# armstrap_eagle-tester_1_0_0.net
KiCad netlist of a schematic drawn in EAGLE
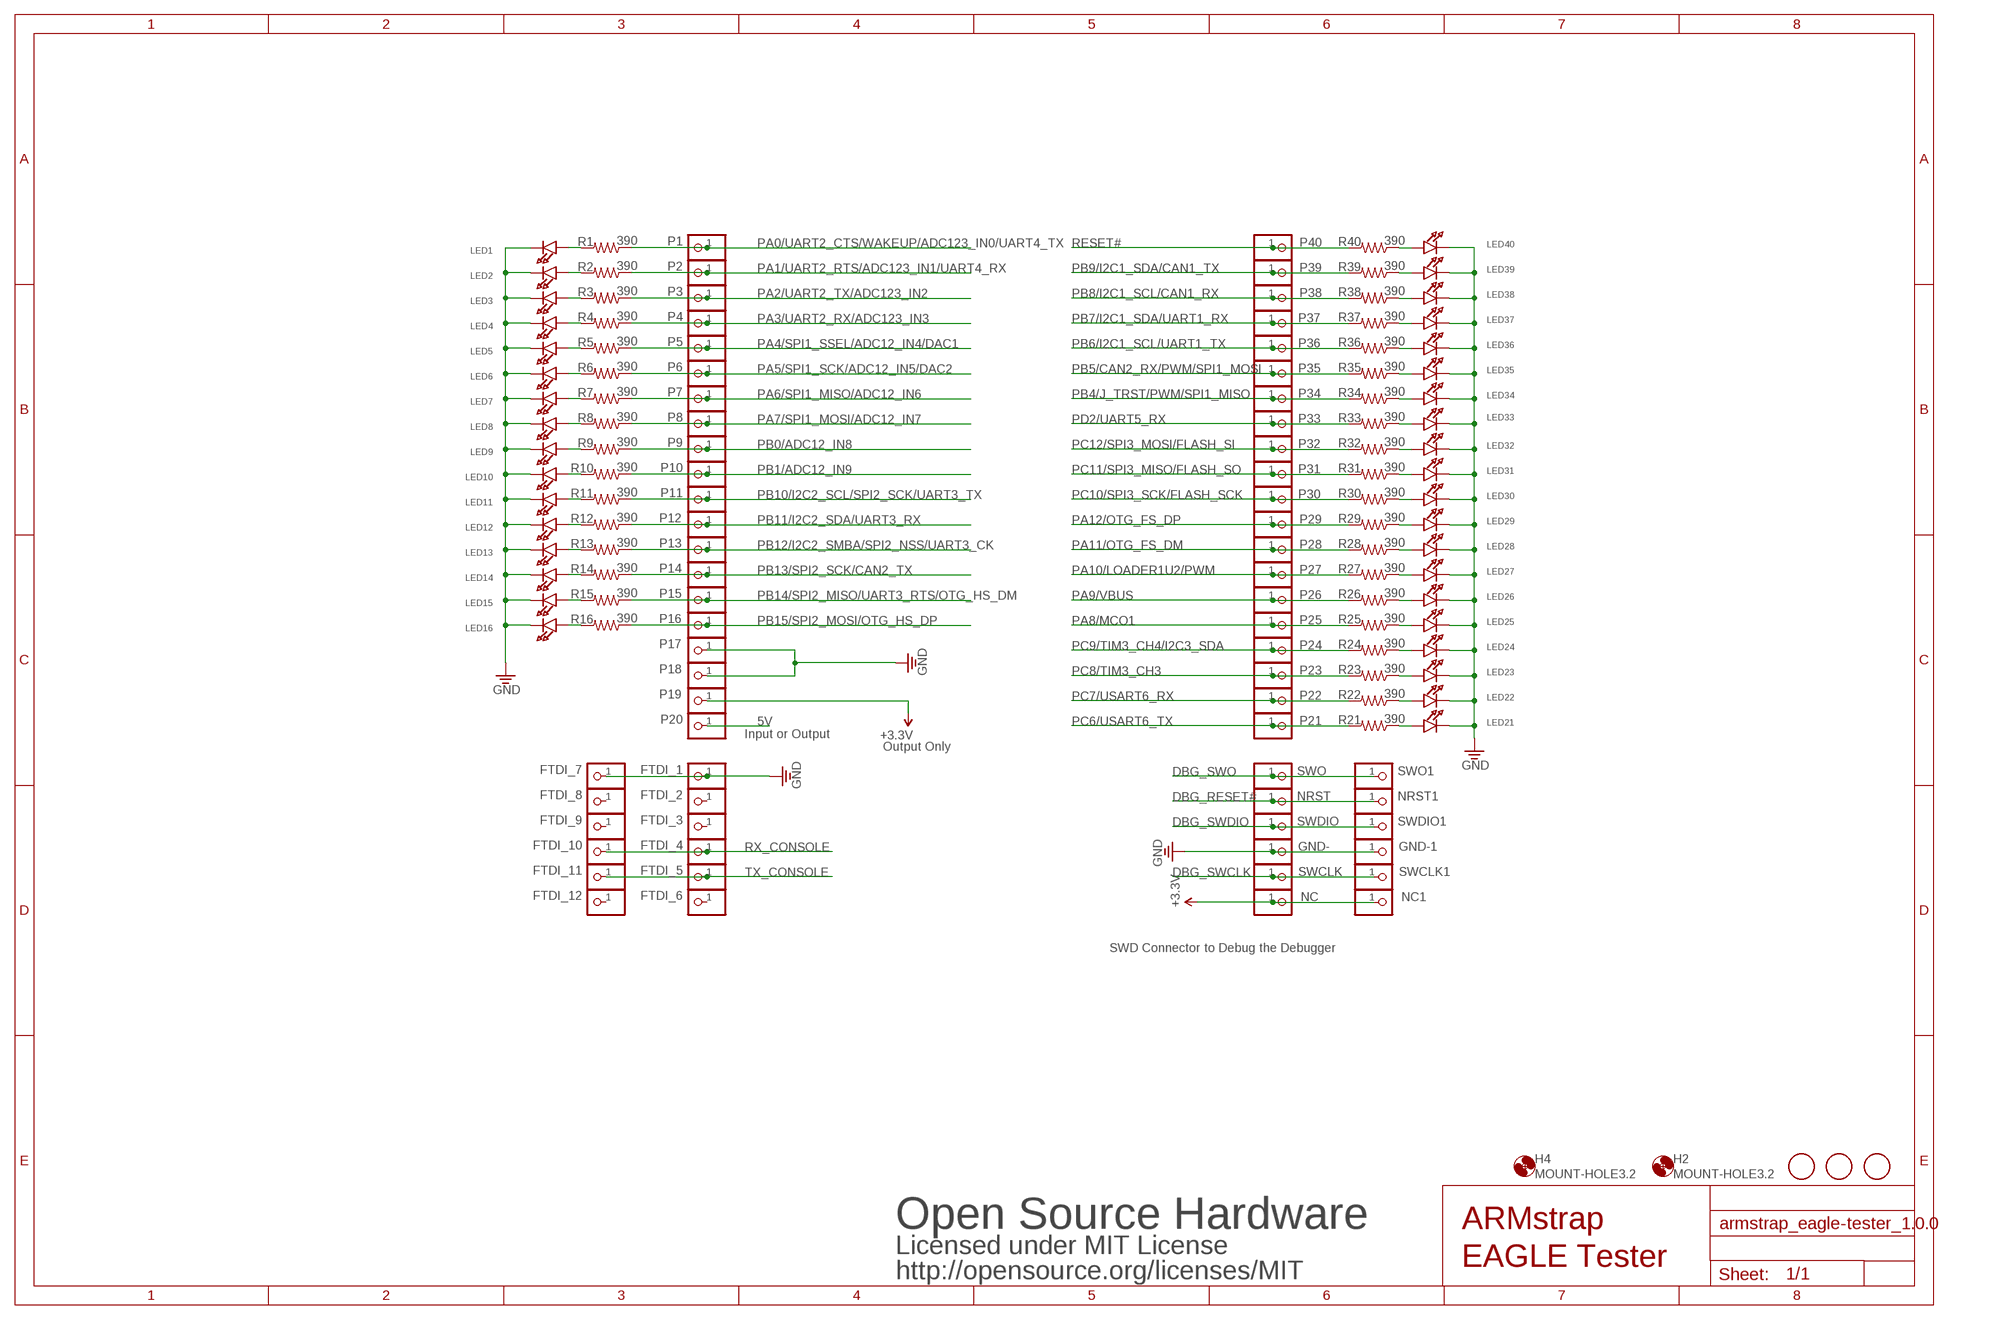
[diagram p0: schematic, sheet 1]

(export (version "E")
  (design (tool "Eeschema 10.0.6"))
  (components
    (comp (ref "FID2")
      (value "FIDUCIAL")
      (footprint "eagle-import:FIDUCIAL_1MM")
      (libsource (lib "eagle-import") (part "FIDUCIAL"))
    )
    (comp (ref "FID3")
      (value "FIDUCIAL")
      (footprint "eagle-import:FIDUCIAL_1MM")
      (libsource (lib "eagle-import") (part "FIDUCIAL"))
    )
    (comp (ref "FID4")
      (value "FIDUCIAL")
      (footprint "eagle-import:FIDUCIAL_1MM")
      (libsource (lib "eagle-import") (part "FIDUCIAL"))
    )
    (comp (ref "FTDI_1")
      (value "PINHD-1X1")
      (footprint "eagle-import:1X01")
      (libsource (lib "eagle-import") (part "PINHD-1X1"))
    )
    (comp (ref "FTDI_2")
      (value "PINHD-1X1")
      (footprint "eagle-import:1X01")
      (libsource (lib "eagle-import") (part "PINHD-1X1"))
    )
    (comp (ref "FTDI_3")
      (value "PINHD-1X1")
      (footprint "eagle-import:1X01")
      (libsource (lib "eagle-import") (part "PINHD-1X1"))
    )
    (comp (ref "FTDI_4")
      (value "PINHD-1X1")
      (footprint "eagle-import:1X01")
      (libsource (lib "eagle-import") (part "PINHD-1X1"))
    )
    (comp (ref "FTDI_5")
      (value "PINHD-1X1")
      (footprint "eagle-import:1X01")
      (libsource (lib "eagle-import") (part "PINHD-1X1"))
    )
    (comp (ref "FTDI_6")
      (value "PINHD-1X1")
      (footprint "eagle-import:1X01")
      (libsource (lib "eagle-import") (part "PINHD-1X1"))
    )
    (comp (ref "FTDI_7")
      (value "PINHD-1X1")
      (footprint "eagle-import:1X01")
      (libsource (lib "eagle-import") (part "PINHD-1X1"))
    )
    (comp (ref "FTDI_8")
      (value "PINHD-1X1")
      (footprint "eagle-import:1X01")
      (libsource (lib "eagle-import") (part "PINHD-1X1"))
    )
    (comp (ref "FTDI_9")
      (value "PINHD-1X1")
      (footprint "eagle-import:1X01")
      (libsource (lib "eagle-import") (part "PINHD-1X1"))
    )
    (comp (ref "FTDI_10")
      (value "PINHD-1X1")
      (footprint "eagle-import:1X01")
      (libsource (lib "eagle-import") (part "PINHD-1X1"))
    )
    (comp (ref "FTDI_11")
      (value "PINHD-1X1")
      (footprint "eagle-import:1X01")
      (libsource (lib "eagle-import") (part "PINHD-1X1"))
    )
    (comp (ref "FTDI_12")
      (value "PINHD-1X1")
      (footprint "eagle-import:1X01")
      (libsource (lib "eagle-import") (part "PINHD-1X1"))
    )
    (comp (ref "GND-")
      (value "PINHD-1X1")
      (footprint "eagle-import:1X01")
      (libsource (lib "eagle-import") (part "PINHD-1X1"))
    )
    (comp (ref "GND-1")
      (value "PINHD-1X1")
      (footprint "eagle-import:1X01")
      (libsource (lib "eagle-import") (part "PINHD-1X1"))
    )
    (comp (ref "H2")
      (value "MOUNT-HOLE3.2")
      (footprint "eagle-import:3,2")
      (libsource (lib "eagle-import") (part "MOUNT-HOLE3.2"))
    )
    (comp (ref "H4")
      (value "MOUNT-HOLE3.2")
      (footprint "eagle-import:3,2")
      (libsource (lib "eagle-import") (part "MOUNT-HOLE3.2"))
    )
    (comp (ref "LED1")
      (value "APT3216QBC/D")
      (footprint "eagle-import:CHIPLED_1206")
      (libsource (lib "eagle-import") (part "LED1206"))
    )
    (comp (ref "LED2")
      (value "APT3216QBC/D")
      (footprint "eagle-import:CHIPLED_1206")
      (libsource (lib "eagle-import") (part "LED1206"))
    )
    (comp (ref "LED3")
      (value "APT3216QBC/D")
      (footprint "eagle-import:CHIPLED_1206")
      (libsource (lib "eagle-import") (part "LED1206"))
    )
    (comp (ref "LED4")
      (value "APT3216QBC/D")
      (footprint "eagle-import:CHIPLED_1206")
      (libsource (lib "eagle-import") (part "LED1206"))
    )
    (comp (ref "LED5")
      (value "APT3216QBC/D")
      (footprint "eagle-import:CHIPLED_1206")
      (libsource (lib "eagle-import") (part "LED1206"))
    )
    (comp (ref "LED6")
      (value "APT3216QBC/D")
      (footprint "eagle-import:CHIPLED_1206")
      (libsource (lib "eagle-import") (part "LED1206"))
    )
    (comp (ref "LED7")
      (value "APT3216QBC/D")
      (footprint "eagle-import:CHIPLED_1206")
      (libsource (lib "eagle-import") (part "LED1206"))
    )
    (comp (ref "LED8")
      (value "APT3216QBC/D")
      (footprint "eagle-import:CHIPLED_1206")
      (libsource (lib "eagle-import") (part "LED1206"))
    )
    (comp (ref "LED9")
      (value "APT3216QBC/D")
      (footprint "eagle-import:CHIPLED_1206")
      (libsource (lib "eagle-import") (part "LED1206"))
    )
    (comp (ref "LED10")
      (value "APT3216QBC/D")
      (footprint "eagle-import:CHIPLED_1206")
      (libsource (lib "eagle-import") (part "LED1206"))
    )
    (comp (ref "LED11")
      (value "APT3216QBC/D")
      (footprint "eagle-import:CHIPLED_1206")
      (libsource (lib "eagle-import") (part "LED1206"))
    )
    (comp (ref "LED12")
      (value "APT3216QBC/D")
      (footprint "eagle-import:CHIPLED_1206")
      (libsource (lib "eagle-import") (part "LED1206"))
    )
    (comp (ref "LED13")
      (value "APT3216QBC/D")
      (footprint "eagle-import:CHIPLED_1206")
      (libsource (lib "eagle-import") (part "LED1206"))
    )
    (comp (ref "LED14")
      (value "APT3216QBC/D")
      (footprint "eagle-import:CHIPLED_1206")
      (libsource (lib "eagle-import") (part "LED1206"))
    )
    (comp (ref "LED15")
      (value "APT3216QBC/D")
      (footprint "eagle-import:CHIPLED_1206")
      (libsource (lib "eagle-import") (part "LED1206"))
    )
    (comp (ref "LED16")
      (value "APT3216QBC/D")
      (footprint "eagle-import:CHIPLED_1206")
      (libsource (lib "eagle-import") (part "LED1206"))
    )
    (comp (ref "LED21")
      (value "APT3216QBC/D")
      (footprint "eagle-import:CHIPLED_1206")
      (libsource (lib "eagle-import") (part "LED1206"))
    )
    (comp (ref "LED22")
      (value "APT3216QBC/D")
      (footprint "eagle-import:CHIPLED_1206")
      (libsource (lib "eagle-import") (part "LED1206"))
    )
    (comp (ref "LED23")
      (value "APT3216QBC/D")
      (footprint "eagle-import:CHIPLED_1206")
      (libsource (lib "eagle-import") (part "LED1206"))
    )
    (comp (ref "LED24")
      (value "APT3216QBC/D")
      (footprint "eagle-import:CHIPLED_1206")
      (libsource (lib "eagle-import") (part "LED1206"))
    )
    (comp (ref "LED25")
      (value "APT3216QBC/D")
      (footprint "eagle-import:CHIPLED_1206")
      (libsource (lib "eagle-import") (part "LED1206"))
    )
    (comp (ref "LED26")
      (value "APT3216QBC/D")
      (footprint "eagle-import:CHIPLED_1206")
      (libsource (lib "eagle-import") (part "LED1206"))
    )
    (comp (ref "LED27")
      (value "APT3216QBC/D")
      (footprint "eagle-import:CHIPLED_1206")
      (libsource (lib "eagle-import") (part "LED1206"))
    )
    (comp (ref "LED28")
      (value "APT3216QBC/D")
      (footprint "eagle-import:CHIPLED_1206")
      (libsource (lib "eagle-import") (part "LED1206"))
    )
    (comp (ref "LED29")
      (value "APT3216QBC/D")
      (footprint "eagle-import:CHIPLED_1206")
      (libsource (lib "eagle-import") (part "LED1206"))
    )
    (comp (ref "LED30")
      (value "APT3216QBC/D")
      (footprint "eagle-import:CHIPLED_1206")
      (libsource (lib "eagle-import") (part "LED1206"))
    )
    (comp (ref "LED31")
      (value "APT3216QBC/D")
      (footprint "eagle-import:CHIPLED_1206")
      (libsource (lib "eagle-import") (part "LED1206"))
    )
    (comp (ref "LED32")
      (value "APT3216QBC/D")
      (footprint "eagle-import:CHIPLED_1206")
      (libsource (lib "eagle-import") (part "LED1206"))
    )
    (comp (ref "LED33")
      (value "APT3216QBC/D")
      (footprint "eagle-import:CHIPLED_1206")
      (libsource (lib "eagle-import") (part "LED1206"))
    )
    (comp (ref "LED34")
      (value "APT3216QBC/D")
      (footprint "eagle-import:CHIPLED_1206")
      (libsource (lib "eagle-import") (part "LED1206"))
    )
    (comp (ref "LED35")
      (value "APT3216QBC/D")
      (footprint "eagle-import:CHIPLED_1206")
      (libsource (lib "eagle-import") (part "LED1206"))
    )
    (comp (ref "LED36")
      (value "APT3216QBC/D")
      (footprint "eagle-import:CHIPLED_1206")
      (libsource (lib "eagle-import") (part "LED1206"))
    )
    (comp (ref "LED37")
      (value "APT3216QBC/D")
      (footprint "eagle-import:CHIPLED_1206")
      (libsource (lib "eagle-import") (part "LED1206"))
    )
    (comp (ref "LED38")
      (value "APT3216QBC/D")
      (footprint "eagle-import:CHIPLED_1206")
      (libsource (lib "eagle-import") (part "LED1206"))
    )
    (comp (ref "LED39")
      (value "APT3216QBC/D")
      (footprint "eagle-import:CHIPLED_1206")
      (libsource (lib "eagle-import") (part "LED1206"))
    )
    (comp (ref "LED40")
      (value "APT3216QBC/D")
      (footprint "eagle-import:CHIPLED_1206")
      (libsource (lib "eagle-import") (part "LED1206"))
    )
    (comp (ref "NC")
      (value "PINHD-1X1")
      (footprint "eagle-import:1X01")
      (libsource (lib "eagle-import") (part "PINHD-1X1"))
    )
    (comp (ref "NC1")
      (value "PINHD-1X1")
      (footprint "eagle-import:1X01")
      (libsource (lib "eagle-import") (part "PINHD-1X1"))
    )
    (comp (ref "NRST")
      (value "PINHD-1X1")
      (footprint "eagle-import:1X01")
      (libsource (lib "eagle-import") (part "PINHD-1X1"))
    )
    (comp (ref "NRST1")
      (value "PINHD-1X1")
      (footprint "eagle-import:1X01")
      (libsource (lib "eagle-import") (part "PINHD-1X1"))
    )
    (comp (ref "P1")
      (value "PINHD-1X1")
      (footprint "eagle-import:1X01")
      (libsource (lib "eagle-import") (part "PINHD-1X1"))
    )
    (comp (ref "P2")
      (value "PINHD-1X1")
      (footprint "eagle-import:1X01")
      (libsource (lib "eagle-import") (part "PINHD-1X1"))
    )
    (comp (ref "P3")
      (value "PINHD-1X1")
      (footprint "eagle-import:1X01")
      (libsource (lib "eagle-import") (part "PINHD-1X1"))
    )
    (comp (ref "P4")
      (value "PINHD-1X1")
      (footprint "eagle-import:1X01")
      (libsource (lib "eagle-import") (part "PINHD-1X1"))
    )
    (comp (ref "P5")
      (value "PINHD-1X1")
      (footprint "eagle-import:1X01")
      (libsource (lib "eagle-import") (part "PINHD-1X1"))
    )
    (comp (ref "P6")
      (value "PINHD-1X1")
      (footprint "eagle-import:1X01")
      (libsource (lib "eagle-import") (part "PINHD-1X1"))
    )
    (comp (ref "P7")
      (value "PINHD-1X1")
      (footprint "eagle-import:1X01")
      (libsource (lib "eagle-import") (part "PINHD-1X1"))
    )
    (comp (ref "P8")
      (value "PINHD-1X1")
      (footprint "eagle-import:1X01")
      (libsource (lib "eagle-import") (part "PINHD-1X1"))
    )
    (comp (ref "P9")
      (value "PINHD-1X1")
      (footprint "eagle-import:1X01")
      (libsource (lib "eagle-import") (part "PINHD-1X1"))
    )
    (comp (ref "P10")
      (value "PINHD-1X1")
      (footprint "eagle-import:1X01")
      (libsource (lib "eagle-import") (part "PINHD-1X1"))
    )
    (comp (ref "P11")
      (value "PINHD-1X1")
      (footprint "eagle-import:1X01")
      (libsource (lib "eagle-import") (part "PINHD-1X1"))
    )
    (comp (ref "P12")
      (value "PINHD-1X1")
      (footprint "eagle-import:1X01")
      (libsource (lib "eagle-import") (part "PINHD-1X1"))
    )
    (comp (ref "P13")
      (value "PINHD-1X1")
      (footprint "eagle-import:1X01")
      (libsource (lib "eagle-import") (part "PINHD-1X1"))
    )
    (comp (ref "P14")
      (value "PINHD-1X1")
      (footprint "eagle-import:1X01")
      (libsource (lib "eagle-import") (part "PINHD-1X1"))
    )
    (comp (ref "P15")
      (value "PINHD-1X1")
      (footprint "eagle-import:1X01")
      (libsource (lib "eagle-import") (part "PINHD-1X1"))
    )
    (comp (ref "P16")
      (value "PINHD-1X1")
      (footprint "eagle-import:1X01")
      (libsource (lib "eagle-import") (part "PINHD-1X1"))
    )
    (comp (ref "P17")
      (value "PINHD-1X1")
      (footprint "eagle-import:1X01")
      (libsource (lib "eagle-import") (part "PINHD-1X1"))
    )
    (comp (ref "P18")
      (value "PINHD-1X1")
      (footprint "eagle-import:1X01")
      (libsource (lib "eagle-import") (part "PINHD-1X1"))
    )
    (comp (ref "P19")
      (value "PINHD-1X1")
      (footprint "eagle-import:1X01")
      (libsource (lib "eagle-import") (part "PINHD-1X1"))
    )
    (comp (ref "P20")
      (value "PINHD-1X1")
      (footprint "eagle-import:1X01")
      (libsource (lib "eagle-import") (part "PINHD-1X1"))
    )
    (comp (ref "P21")
      (value "PINHD-1X1")
      (footprint "eagle-import:1X01")
      (libsource (lib "eagle-import") (part "PINHD-1X1"))
    )
    (comp (ref "P22")
      (value "PINHD-1X1")
      (footprint "eagle-import:1X01")
      (libsource (lib "eagle-import") (part "PINHD-1X1"))
    )
    (comp (ref "P23")
      (value "PINHD-1X1")
      (footprint "eagle-import:1X01")
      (libsource (lib "eagle-import") (part "PINHD-1X1"))
    )
    (comp (ref "P24")
      (value "PINHD-1X1")
      (footprint "eagle-import:1X01")
      (libsource (lib "eagle-import") (part "PINHD-1X1"))
    )
    (comp (ref "P25")
      (value "PINHD-1X1")
      (footprint "eagle-import:1X01")
      (libsource (lib "eagle-import") (part "PINHD-1X1"))
    )
    (comp (ref "P26")
      (value "PINHD-1X1")
      (footprint "eagle-import:1X01")
      (libsource (lib "eagle-import") (part "PINHD-1X1"))
    )
    (comp (ref "P27")
      (value "PINHD-1X1")
      (footprint "eagle-import:1X01")
      (libsource (lib "eagle-import") (part "PINHD-1X1"))
    )
    (comp (ref "P28")
      (value "PINHD-1X1")
      (footprint "eagle-import:1X01")
      (libsource (lib "eagle-import") (part "PINHD-1X1"))
    )
    (comp (ref "P29")
      (value "PINHD-1X1")
      (footprint "eagle-import:1X01")
      (libsource (lib "eagle-import") (part "PINHD-1X1"))
    )
    (comp (ref "P30")
      (value "PINHD-1X1")
      (footprint "eagle-import:1X01")
      (libsource (lib "eagle-import") (part "PINHD-1X1"))
    )
    (comp (ref "P31")
      (value "PINHD-1X1")
      (footprint "eagle-import:1X01")
      (libsource (lib "eagle-import") (part "PINHD-1X1"))
    )
    (comp (ref "P32")
      (value "PINHD-1X1")
      (footprint "eagle-import:1X01")
      (libsource (lib "eagle-import") (part "PINHD-1X1"))
    )
    (comp (ref "P33")
      (value "PINHD-1X1")
      (footprint "eagle-import:1X01")
      (libsource (lib "eagle-import") (part "PINHD-1X1"))
    )
    (comp (ref "P34")
      (value "PINHD-1X1")
      (footprint "eagle-import:1X01")
      (libsource (lib "eagle-import") (part "PINHD-1X1"))
    )
    (comp (ref "P35")
      (value "PINHD-1X1")
      (footprint "eagle-import:1X01")
      (libsource (lib "eagle-import") (part "PINHD-1X1"))
    )
    (comp (ref "P36")
      (value "PINHD-1X1")
      (footprint "eagle-import:1X01")
      (libsource (lib "eagle-import") (part "PINHD-1X1"))
    )
    (comp (ref "P37")
      (value "PINHD-1X1")
      (footprint "eagle-import:1X01")
      (libsource (lib "eagle-import") (part "PINHD-1X1"))
    )
    (comp (ref "P38")
      (value "PINHD-1X1")
      (footprint "eagle-import:1X01")
      (libsource (lib "eagle-import") (part "PINHD-1X1"))
    )
    (comp (ref "P39")
      (value "PINHD-1X1")
      (footprint "eagle-import:1X01")
      (libsource (lib "eagle-import") (part "PINHD-1X1"))
    )
    (comp (ref "P40")
      (value "PINHD-1X1")
      (footprint "eagle-import:1X01")
      (libsource (lib "eagle-import") (part "PINHD-1X1"))
    )
    (comp (ref "R1")
      (value "390")
      (footprint "eagle-import:0805")
      (libsource (lib "eagle-import") (part "RES0805"))
    )
    (comp (ref "R2")
      (value "390")
      (footprint "eagle-import:0805")
      (libsource (lib "eagle-import") (part "RES0805"))
    )
    (comp (ref "R3")
      (value "390")
      (footprint "eagle-import:0805")
      (libsource (lib "eagle-import") (part "RES0805"))
    )
    (comp (ref "R4")
      (value "390")
      (footprint "eagle-import:0805")
      (libsource (lib "eagle-import") (part "RES0805"))
    )
    (comp (ref "R5")
      (value "390")
      (footprint "eagle-import:0805")
      (libsource (lib "eagle-import") (part "RES0805"))
    )
    (comp (ref "R6")
      (value "390")
      (footprint "eagle-import:0805")
      (libsource (lib "eagle-import") (part "RES0805"))
    )
    (comp (ref "R7")
      (value "390")
      (footprint "eagle-import:0805")
      (libsource (lib "eagle-import") (part "RES0805"))
    )
    (comp (ref "R8")
      (value "390")
      (footprint "eagle-import:0805")
      (libsource (lib "eagle-import") (part "RES0805"))
    )
    (comp (ref "R9")
      (value "390")
      (footprint "eagle-import:0805")
      (libsource (lib "eagle-import") (part "RES0805"))
    )
    (comp (ref "R10")
      (value "390")
      (footprint "eagle-import:0805")
      (libsource (lib "eagle-import") (part "RES0805"))
    )
    (comp (ref "R11")
      (value "390")
      (footprint "eagle-import:0805")
      (libsource (lib "eagle-import") (part "RES0805"))
    )
    (comp (ref "R12")
      (value "390")
      (footprint "eagle-import:0805")
      (libsource (lib "eagle-import") (part "RES0805"))
    )
    (comp (ref "R13")
      (value "390")
      (footprint "eagle-import:0805")
      (libsource (lib "eagle-import") (part "RES0805"))
    )
    (comp (ref "R14")
      (value "390")
      (footprint "eagle-import:0805")
      (libsource (lib "eagle-import") (part "RES0805"))
    )
    (comp (ref "R15")
      (value "390")
      (footprint "eagle-import:0805")
      (libsource (lib "eagle-import") (part "RES0805"))
    )
    (comp (ref "R16")
      (value "390")
      (footprint "eagle-import:0805")
      (libsource (lib "eagle-import") (part "RES0805"))
    )
    (comp (ref "R21")
      (value "390")
      (footprint "eagle-import:0805")
      (libsource (lib "eagle-import") (part "RES0805"))
    )
    (comp (ref "R22")
      (value "390")
      (footprint "eagle-import:0805")
      (libsource (lib "eagle-import") (part "RES0805"))
    )
    (comp (ref "R23")
      (value "390")
      (footprint "eagle-import:0805")
      (libsource (lib "eagle-import") (part "RES0805"))
    )
    (comp (ref "R24")
      (value "390")
      (footprint "eagle-import:0805")
      (libsource (lib "eagle-import") (part "RES0805"))
    )
    (comp (ref "R25")
      (value "390")
      (footprint "eagle-import:0805")
      (libsource (lib "eagle-import") (part "RES0805"))
    )
    (comp (ref "R26")
      (value "390")
      (footprint "eagle-import:0805")
      (libsource (lib "eagle-import") (part "RES0805"))
    )
    (comp (ref "R27")
      (value "390")
      (footprint "eagle-import:0805")
      (libsource (lib "eagle-import") (part "RES0805"))
    )
    (comp (ref "R28")
      (value "390")
      (footprint "eagle-import:0805")
      (libsource (lib "eagle-import") (part "RES0805"))
    )
    (comp (ref "R29")
      (value "390")
      (footprint "eagle-import:0805")
      (libsource (lib "eagle-import") (part "RES0805"))
    )
    (comp (ref "R30")
      (value "390")
      (footprint "eagle-import:0805")
      (libsource (lib "eagle-import") (part "RES0805"))
    )
    (comp (ref "R31")
      (value "390")
      (footprint "eagle-import:0805")
      (libsource (lib "eagle-import") (part "RES0805"))
    )
    (comp (ref "R32")
      (value "390")
      (footprint "eagle-import:0805")
      (libsource (lib "eagle-import") (part "RES0805"))
    )
    (comp (ref "R33")
      (value "390")
      (footprint "eagle-import:0805")
      (libsource (lib "eagle-import") (part "RES0805"))
    )
    (comp (ref "R34")
      (value "390")
      (footprint "eagle-import:0805")
      (libsource (lib "eagle-import") (part "RES0805"))
    )
    (comp (ref "R35")
      (value "390")
      (footprint "eagle-import:0805")
      (libsource (lib "eagle-import") (part "RES0805"))
    )
    (comp (ref "R36")
      (value "390")
      (footprint "eagle-import:0805")
      (libsource (lib "eagle-import") (part "RES0805"))
    )
    (comp (ref "R37")
      (value "390")
      (footprint "eagle-import:0805")
      (libsource (lib "eagle-import") (part "RES0805"))
    )
    (comp (ref "R38")
      (value "390")
      (footprint "eagle-import:0805")
      (libsource (lib "eagle-import") (part "RES0805"))
    )
    (comp (ref "R39")
      (value "390")
      (footprint "eagle-import:0805")
      (libsource (lib "eagle-import") (part "RES0805"))
    )
    (comp (ref "R40")
      (value "390")
      (footprint "eagle-import:0805")
      (libsource (lib "eagle-import") (part "RES0805"))
    )
    (comp (ref "SWCLK")
      (value "PINHD-1X1")
      (footprint "eagle-import:1X01")
      (libsource (lib "eagle-import") (part "PINHD-1X1"))
    )
    (comp (ref "SWCLK1")
      (value "PINHD-1X1")
      (footprint "eagle-import:1X01")
      (libsource (lib "eagle-import") (part "PINHD-1X1"))
    )
    (comp (ref "SWDIO")
      (value "PINHD-1X1")
      (footprint "eagle-import:1X01")
      (libsource (lib "eagle-import") (part "PINHD-1X1"))
    )
    (comp (ref "SWDIO1")
      (value "PINHD-1X1")
      (footprint "eagle-import:1X01")
      (libsource (lib "eagle-import") (part "PINHD-1X1"))
    )
    (comp (ref "SWO")
      (value "PINHD-1X1")
      (footprint "eagle-import:1X01")
      (libsource (lib "eagle-import") (part "PINHD-1X1"))
    )
    (comp (ref "SWO1")
      (value "PINHD-1X1")
      (footprint "eagle-import:1X01")
      (libsource (lib "eagle-import") (part "PINHD-1X1"))
    )
  )
  (nets
    (net (code "1") (name "+3.3V") (class "Default")
      (node (ref "NC") (pin "1") (pinfunction "1_1") (pintype "passive"))
      (node (ref "NC1") (pin "1") (pinfunction "1_1") (pintype "passive"))
      (node (ref "P19") (pin "1") (pinfunction "1_1") (pintype "passive"))
    )
    (net (code "2") (name "/5V") (class "Default")
      (node (ref "P20") (pin "1") (pinfunction "1_1") (pintype "passive"))
    )
    (net (code "3") (name "/DBG_RESET#") (class "Default")
      (node (ref "NRST") (pin "1") (pinfunction "1_1") (pintype "passive"))
      (node (ref "NRST1") (pin "1") (pinfunction "1_1") (pintype "passive"))
    )
    (net (code "4") (name "/DBG_SWCLK") (class "Default")
      (node (ref "SWCLK") (pin "1") (pinfunction "1_1") (pintype "passive"))
      (node (ref "SWCLK1") (pin "1") (pinfunction "1_1") (pintype "passive"))
    )
    (net (code "5") (name "/DBG_SWDIO") (class "Default")
      (node (ref "SWDIO") (pin "1") (pinfunction "1_1") (pintype "passive"))
      (node (ref "SWDIO1") (pin "1") (pinfunction "1_1") (pintype "passive"))
    )
    (net (code "6") (name "/DBG_SWO") (class "Default")
      (node (ref "SWO") (pin "1") (pinfunction "1_1") (pintype "passive"))
      (node (ref "SWO1") (pin "1") (pinfunction "1_1") (pintype "passive"))
    )
    (net (code "7") (name "/PA0{slash}UART2_CTS{slash}WAKEUP{slash}ADC123_IN0{slash}UART4_TX") (class "Default")
      (node (ref "P1") (pin "1") (pinfunction "1_1") (pintype "passive"))
      (node (ref "R1") (pin "1") (pinfunction "1_1") (pintype "passive"))
    )
    (net (code "8") (name "/PA1{slash}UART2_RTS{slash}ADC123_IN1{slash}UART4_RX") (class "Default")
      (node (ref "P2") (pin "1") (pinfunction "1_1") (pintype "passive"))
      (node (ref "R2") (pin "1") (pinfunction "1_1") (pintype "passive"))
    )
    (net (code "9") (name "/PA2{slash}UART2_TX{slash}ADC123_IN2") (class "Default")
      (node (ref "P3") (pin "1") (pinfunction "1_1") (pintype "passive"))
      (node (ref "R3") (pin "1") (pinfunction "1_1") (pintype "passive"))
    )
    (net (code "10") (name "/PA3{slash}UART2_RX{slash}ADC123_IN3") (class "Default")
      (node (ref "P4") (pin "1") (pinfunction "1_1") (pintype "passive"))
      (node (ref "R4") (pin "1") (pinfunction "1_1") (pintype "passive"))
    )
    (net (code "11") (name "/PA4{slash}SPI1_SSEL{slash}ADC12_IN4{slash}DAC1") (class "Default")
      (node (ref "P5") (pin "1") (pinfunction "1_1") (pintype "passive"))
      (node (ref "R5") (pin "1") (pinfunction "1_1") (pintype "passive"))
    )
    (net (code "12") (name "/PA5{slash}SPI1_SCK{slash}ADC12_IN5{slash}DAC2") (class "Default")
      (node (ref "P6") (pin "1") (pinfunction "1_1") (pintype "passive"))
      (node (ref "R6") (pin "1") (pinfunction "1_1") (pintype "passive"))
    )
    (net (code "13") (name "/PA6{slash}SPI1_MISO{slash}ADC12_IN6") (class "Default")
      (node (ref "P7") (pin "1") (pinfunction "1_1") (pintype "passive"))
      (node (ref "R7") (pin "1") (pinfunction "1_1") (pintype "passive"))
    )
    (net (code "14") (name "/PA7{slash}SPI1_MOSI{slash}ADC12_IN7") (class "Default")
      (node (ref "P8") (pin "1") (pinfunction "1_1") (pintype "passive"))
      (node (ref "R8") (pin "1") (pinfunction "1_1") (pintype "passive"))
    )
    (net (code "15") (name "/PA8{slash}MCO1") (class "Default")
      (node (ref "P25") (pin "1") (pinfunction "1_1") (pintype "passive"))
      (node (ref "R25") (pin "2") (pinfunction "2_2") (pintype "passive"))
    )
    (net (code "16") (name "/PA9{slash}VBUS") (class "Default")
      (node (ref "P26") (pin "1") (pinfunction "1_1") (pintype "passive"))
      (node (ref "R26") (pin "2") (pinfunction "2_2") (pintype "passive"))
    )
    (net (code "17") (name "/PA10{slash}LOADER1U2{slash}PWM") (class "Default")
      (node (ref "P27") (pin "1") (pinfunction "1_1") (pintype "passive"))
      (node (ref "R27") (pin "2") (pinfunction "2_2") (pintype "passive"))
    )
    (net (code "18") (name "/PA11{slash}OTG_FS_DM") (class "Default")
      (node (ref "P28") (pin "1") (pinfunction "1_1") (pintype "passive"))
      (node (ref "R28") (pin "2") (pinfunction "2_2") (pintype "passive"))
    )
    (net (code "19") (name "/PA12{slash}OTG_FS_DP") (class "Default")
      (node (ref "P29") (pin "1") (pinfunction "1_1") (pintype "passive"))
      (node (ref "R29") (pin "2") (pinfunction "2_2") (pintype "passive"))
    )
    (net (code "20") (name "/PB0{slash}ADC12_IN8") (class "Default")
      (node (ref "P9") (pin "1") (pinfunction "1_1") (pintype "passive"))
      (node (ref "R9") (pin "1") (pinfunction "1_1") (pintype "passive"))
    )
    (net (code "21") (name "/PB1{slash}ADC12_IN9") (class "Default")
      (node (ref "P10") (pin "1") (pinfunction "1_1") (pintype "passive"))
      (node (ref "R10") (pin "1") (pinfunction "1_1") (pintype "passive"))
    )
    (net (code "22") (name "/PB4{slash}J_TRST{slash}PWM{slash}SPI1_MISO") (class "Default")
      (node (ref "P34") (pin "1") (pinfunction "1_1") (pintype "passive"))
      (node (ref "R34") (pin "2") (pinfunction "2_2") (pintype "passive"))
    )
    (net (code "23") (name "/PB5{slash}CAN2_RX{slash}PWM{slash}SPI1_MOSI") (class "Default")
      (node (ref "P35") (pin "1") (pinfunction "1_1") (pintype "passive"))
      (node (ref "R35") (pin "2") (pinfunction "2_2") (pintype "passive"))
    )
    (net (code "24") (name "/PB6{slash}I2C1_SCL{slash}UART1_TX") (class "Default")
      (node (ref "P36") (pin "1") (pinfunction "1_1") (pintype "passive"))
      (node (ref "R36") (pin "2") (pinfunction "2_2") (pintype "passive"))
    )
    (net (code "25") (name "/PB7{slash}I2C1_SDA{slash}UART1_RX") (class "Default")
      (node (ref "P37") (pin "1") (pinfunction "1_1") (pintype "passive"))
      (node (ref "R37") (pin "2") (pinfunction "2_2") (pintype "passive"))
    )
    (net (code "26") (name "/PB8{slash}I2C1_SCL{slash}CAN1_RX") (class "Default")
      (node (ref "P38") (pin "1") (pinfunction "1_1") (pintype "passive"))
      (node (ref "R38") (pin "2") (pinfunction "2_2") (pintype "passive"))
    )
    (net (code "27") (name "/PB9{slash}I2C1_SDA{slash}CAN1_TX") (class "Default")
      (node (ref "P39") (pin "1") (pinfunction "1_1") (pintype "passive"))
      (node (ref "R39") (pin "2") (pinfunction "2_2") (pintype "passive"))
    )
    (net (code "28") (name "/PB10{slash}I2C2_SCL{slash}SPI2_SCK{slash}UART3_TX") (class "Default")
      (node (ref "P11") (pin "1") (pinfunction "1_1") (pintype "passive"))
      (node (ref "R11") (pin "1") (pinfunction "1_1") (pintype "passive"))
    )
    (net (code "29") (name "/PB11{slash}I2C2_SDA{slash}UART3_RX") (class "Default")
      (node (ref "P12") (pin "1") (pinfunction "1_1") (pintype "passive"))
      (node (ref "R12") (pin "1") (pinfunction "1_1") (pintype "passive"))
    )
    (net (code "30") (name "/PB12{slash}I2C2_SMBA{slash}SPI2_NSS{slash}UART3_CK") (class "Default")
      (node (ref "P13") (pin "1") (pinfunction "1_1") (pintype "passive"))
      (node (ref "R13") (pin "1") (pinfunction "1_1") (pintype "passive"))
    )
    (net (code "31") (name "/PB13{slash}SPI2_SCK{slash}CAN2_TX") (class "Default")
      (node (ref "P14") (pin "1") (pinfunction "1_1") (pintype "passive"))
      (node (ref "R14") (pin "1") (pinfunction "1_1") (pintype "passive"))
    )
    (net (code "32") (name "/PB14{slash}SPI2_MISO{slash}UART3_RTS{slash}OTG_HS_DM") (class "Default")
      (node (ref "P15") (pin "1") (pinfunction "1_1") (pintype "passive"))
      (node (ref "R15") (pin "1") (pinfunction "1_1") (pintype "passive"))
    )
    (net (code "33") (name "/PB15{slash}SPI2_MOSI{slash}OTG_HS_DP") (class "Default")
      (node (ref "P16") (pin "1") (pinfunction "1_1") (pintype "passive"))
      (node (ref "R16") (pin "1") (pinfunction "1_1") (pintype "passive"))
    )
    (net (code "34") (name "/PC6{slash}USART6_TX") (class "Default")
      (node (ref "P21") (pin "1") (pinfunction "1_1") (pintype "passive"))
      (node (ref "R21") (pin "2") (pinfunction "2_2") (pintype "passive"))
    )
    (net (code "35") (name "/PC7{slash}USART6_RX") (class "Default")
      (node (ref "P22") (pin "1") (pinfunction "1_1") (pintype "passive"))
      (node (ref "R22") (pin "2") (pinfunction "2_2") (pintype "passive"))
    )
    (net (code "36") (name "/PC8{slash}TIM3_CH3") (class "Default")
      (node (ref "P23") (pin "1") (pinfunction "1_1") (pintype "passive"))
      (node (ref "R23") (pin "2") (pinfunction "2_2") (pintype "passive"))
    )
    (net (code "37") (name "/PC9{slash}TIM3_CH4{slash}I2C3_SDA") (class "Default")
      (node (ref "P24") (pin "1") (pinfunction "1_1") (pintype "passive"))
      (node (ref "R24") (pin "2") (pinfunction "2_2") (pintype "passive"))
    )
    (net (code "38") (name "/PC10{slash}SPI3_SCK{slash}FLASH_SCK") (class "Default")
      (node (ref "P30") (pin "1") (pinfunction "1_1") (pintype "passive"))
      (node (ref "R30") (pin "2") (pinfunction "2_2") (pintype "passive"))
    )
    (net (code "39") (name "/PC11{slash}SPI3_MISO{slash}FLASH_SO") (class "Default")
      (node (ref "P31") (pin "1") (pinfunction "1_1") (pintype "passive"))
      (node (ref "R31") (pin "2") (pinfunction "2_2") (pintype "passive"))
    )
    (net (code "40") (name "/PC12{slash}SPI3_MOSI{slash}FLASH_SI") (class "Default")
      (node (ref "P32") (pin "1") (pinfunction "1_1") (pintype "passive"))
      (node (ref "R32") (pin "2") (pinfunction "2_2") (pintype "passive"))
    )
    (net (code "41") (name "/PD2{slash}UART5_RX") (class "Default")
      (node (ref "P33") (pin "1") (pinfunction "1_1") (pintype "passive"))
      (node (ref "R33") (pin "2") (pinfunction "2_2") (pintype "passive"))
    )
    (net (code "42") (name "/RESET#") (class "Default")
      (node (ref "P40") (pin "1") (pinfunction "1_1") (pintype "passive"))
      (node (ref "R40") (pin "2") (pinfunction "2_2") (pintype "passive"))
    )
    (net (code "43") (name "/RX_CONSOLE") (class "Default")
      (node (ref "FTDI_10") (pin "1") (pinfunction "1_1") (pintype "passive"))
      (node (ref "FTDI_4") (pin "1") (pinfunction "1_1") (pintype "passive"))
    )
    (net (code "44") (name "/TX_CONSOLE") (class "Default")
      (node (ref "FTDI_11") (pin "1") (pinfunction "1_1") (pintype "passive"))
      (node (ref "FTDI_5") (pin "1") (pinfunction "1_1") (pintype "passive"))
    )
    (net (code "45") (name "GND") (class "Default")
      (node (ref "FTDI_1") (pin "1") (pinfunction "1_1") (pintype "passive"))
      (node (ref "FTDI_7") (pin "1") (pinfunction "1_1") (pintype "passive"))
      (node (ref "GND-") (pin "1") (pinfunction "1_1") (pintype "passive"))
      (node (ref "GND-1") (pin "1") (pinfunction "1_1") (pintype "passive"))
      (node (ref "LED1") (pin "C") (pinfunction "C_C") (pintype "passive"))
      (node (ref "LED10") (pin "C") (pinfunction "C_C") (pintype "passive"))
      (node (ref "LED11") (pin "C") (pinfunction "C_C") (pintype "passive"))
      (node (ref "LED12") (pin "C") (pinfunction "C_C") (pintype "passive"))
      (node (ref "LED13") (pin "C") (pinfunction "C_C") (pintype "passive"))
      (node (ref "LED14") (pin "C") (pinfunction "C_C") (pintype "passive"))
      (node (ref "LED15") (pin "C") (pinfunction "C_C") (pintype "passive"))
      (node (ref "LED16") (pin "C") (pinfunction "C_C") (pintype "passive"))
      (node (ref "LED2") (pin "C") (pinfunction "C_C") (pintype "passive"))
      (node (ref "LED21") (pin "C") (pinfunction "C_C") (pintype "passive"))
      (node (ref "LED22") (pin "C") (pinfunction "C_C") (pintype "passive"))
      (node (ref "LED23") (pin "C") (pinfunction "C_C") (pintype "passive"))
      (node (ref "LED24") (pin "C") (pinfunction "C_C") (pintype "passive"))
      (node (ref "LED25") (pin "C") (pinfunction "C_C") (pintype "passive"))
      (node (ref "LED26") (pin "C") (pinfunction "C_C") (pintype "passive"))
      (node (ref "LED27") (pin "C") (pinfunction "C_C") (pintype "passive"))
      (node (ref "LED28") (pin "C") (pinfunction "C_C") (pintype "passive"))
      (node (ref "LED29") (pin "C") (pinfunction "C_C") (pintype "passive"))
      (node (ref "LED3") (pin "C") (pinfunction "C_C") (pintype "passive"))
      (node (ref "LED30") (pin "C") (pinfunction "C_C") (pintype "passive"))
      (node (ref "LED31") (pin "C") (pinfunction "C_C") (pintype "passive"))
      (node (ref "LED32") (pin "C") (pinfunction "C_C") (pintype "passive"))
      (node (ref "LED33") (pin "C") (pinfunction "C_C") (pintype "passive"))
      (node (ref "LED34") (pin "C") (pinfunction "C_C") (pintype "passive"))
      (node (ref "LED35") (pin "C") (pinfunction "C_C") (pintype "passive"))
      (node (ref "LED36") (pin "C") (pinfunction "C_C") (pintype "passive"))
      (node (ref "LED37") (pin "C") (pinfunction "C_C") (pintype "passive"))
      (node (ref "LED38") (pin "C") (pinfunction "C_C") (pintype "passive"))
      (node (ref "LED39") (pin "C") (pinfunction "C_C") (pintype "passive"))
      (node (ref "LED4") (pin "C") (pinfunction "C_C") (pintype "passive"))
      (node (ref "LED40") (pin "C") (pinfunction "C_C") (pintype "passive"))
      (node (ref "LED5") (pin "C") (pinfunction "C_C") (pintype "passive"))
      (node (ref "LED6") (pin "C") (pinfunction "C_C") (pintype "passive"))
      (node (ref "LED7") (pin "C") (pinfunction "C_C") (pintype "passive"))
      (node (ref "LED8") (pin "C") (pinfunction "C_C") (pintype "passive"))
      (node (ref "LED9") (pin "C") (pinfunction "C_C") (pintype "passive"))
      (node (ref "P17") (pin "1") (pinfunction "1_1") (pintype "passive"))
      (node (ref "P18") (pin "1") (pinfunction "1_1") (pintype "passive"))
    )
    (net (code "46") (name "Net-(LED1-PadA)") (class "Default")
      (node (ref "LED1") (pin "A") (pinfunction "A_A") (pintype "passive"))
      (node (ref "R1") (pin "2") (pinfunction "2_2") (pintype "passive"))
    )
    (net (code "47") (name "Net-(LED2-PadA)") (class "Default")
      (node (ref "LED2") (pin "A") (pinfunction "A_A") (pintype "passive"))
      (node (ref "R2") (pin "2") (pinfunction "2_2") (pintype "passive"))
    )
    (net (code "48") (name "Net-(LED3-PadA)") (class "Default")
      (node (ref "LED3") (pin "A") (pinfunction "A_A") (pintype "passive"))
      (node (ref "R3") (pin "2") (pinfunction "2_2") (pintype "passive"))
    )
    (net (code "49") (name "Net-(LED4-PadA)") (class "Default")
      (node (ref "LED4") (pin "A") (pinfunction "A_A") (pintype "passive"))
      (node (ref "R4") (pin "2") (pinfunction "2_2") (pintype "passive"))
    )
    (net (code "50") (name "Net-(LED5-PadA)") (class "Default")
      (node (ref "LED5") (pin "A") (pinfunction "A_A") (pintype "passive"))
      (node (ref "R5") (pin "2") (pinfunction "2_2") (pintype "passive"))
    )
    (net (code "51") (name "Net-(LED6-PadA)") (class "Default")
      (node (ref "LED6") (pin "A") (pinfunction "A_A") (pintype "passive"))
      (node (ref "R6") (pin "2") (pinfunction "2_2") (pintype "passive"))
    )
    (net (code "52") (name "Net-(LED7-PadA)") (class "Default")
      (node (ref "LED7") (pin "A") (pinfunction "A_A") (pintype "passive"))
      (node (ref "R7") (pin "2") (pinfunction "2_2") (pintype "passive"))
    )
    (net (code "53") (name "Net-(LED8-PadA)") (class "Default")
      (node (ref "LED8") (pin "A") (pinfunction "A_A") (pintype "passive"))
      (node (ref "R8") (pin "2") (pinfunction "2_2") (pintype "passive"))
    )
    (net (code "54") (name "Net-(LED9-PadA)") (class "Default")
      (node (ref "LED9") (pin "A") (pinfunction "A_A") (pintype "passive"))
      (node (ref "R9") (pin "2") (pinfunction "2_2") (pintype "passive"))
    )
    (net (code "55") (name "Net-(LED10-PadA)") (class "Default")
      (node (ref "LED10") (pin "A") (pinfunction "A_A") (pintype "passive"))
      (node (ref "R10") (pin "2") (pinfunction "2_2") (pintype "passive"))
    )
    (net (code "56") (name "Net-(LED11-PadA)") (class "Default")
      (node (ref "LED11") (pin "A") (pinfunction "A_A") (pintype "passive"))
      (node (ref "R11") (pin "2") (pinfunction "2_2") (pintype "passive"))
    )
    (net (code "57") (name "Net-(LED12-PadA)") (class "Default")
      (node (ref "LED12") (pin "A") (pinfunction "A_A") (pintype "passive"))
      (node (ref "R12") (pin "2") (pinfunction "2_2") (pintype "passive"))
    )
    (net (code "58") (name "Net-(LED13-PadA)") (class "Default")
      (node (ref "LED13") (pin "A") (pinfunction "A_A") (pintype "passive"))
      (node (ref "R13") (pin "2") (pinfunction "2_2") (pintype "passive"))
    )
    (net (code "59") (name "Net-(LED14-PadA)") (class "Default")
      (node (ref "LED14") (pin "A") (pinfunction "A_A") (pintype "passive"))
      (node (ref "R14") (pin "2") (pinfunction "2_2") (pintype "passive"))
    )
    (net (code "60") (name "Net-(LED15-PadA)") (class "Default")
      (node (ref "LED15") (pin "A") (pinfunction "A_A") (pintype "passive"))
      (node (ref "R15") (pin "2") (pinfunction "2_2") (pintype "passive"))
    )
    (net (code "61") (name "Net-(LED16-PadA)") (class "Default")
      (node (ref "LED16") (pin "A") (pinfunction "A_A") (pintype "passive"))
      (node (ref "R16") (pin "2") (pinfunction "2_2") (pintype "passive"))
    )
    (net (code "62") (name "Net-(LED21-PadA)") (class "Default")
      (node (ref "LED21") (pin "A") (pinfunction "A_A") (pintype "passive"))
      (node (ref "R21") (pin "1") (pinfunction "1_1") (pintype "passive"))
    )
    (net (code "63") (name "Net-(LED22-PadA)") (class "Default")
      (node (ref "LED22") (pin "A") (pinfunction "A_A") (pintype "passive"))
      (node (ref "R22") (pin "1") (pinfunction "1_1") (pintype "passive"))
    )
    (net (code "64") (name "Net-(LED23-PadA)") (class "Default")
      (node (ref "LED23") (pin "A") (pinfunction "A_A") (pintype "passive"))
      (node (ref "R23") (pin "1") (pinfunction "1_1") (pintype "passive"))
    )
    (net (code "65") (name "Net-(LED24-PadA)") (class "Default")
      (node (ref "LED24") (pin "A") (pinfunction "A_A") (pintype "passive"))
      (node (ref "R24") (pin "1") (pinfunction "1_1") (pintype "passive"))
    )
    (net (code "66") (name "Net-(LED25-PadA)") (class "Default")
      (node (ref "LED25") (pin "A") (pinfunction "A_A") (pintype "passive"))
      (node (ref "R25") (pin "1") (pinfunction "1_1") (pintype "passive"))
    )
    (net (code "67") (name "Net-(LED26-PadA)") (class "Default")
      (node (ref "LED26") (pin "A") (pinfunction "A_A") (pintype "passive"))
      (node (ref "R26") (pin "1") (pinfunction "1_1") (pintype "passive"))
    )
    (net (code "68") (name "Net-(LED27-PadA)") (class "Default")
      (node (ref "LED27") (pin "A") (pinfunction "A_A") (pintype "passive"))
      (node (ref "R27") (pin "1") (pinfunction "1_1") (pintype "passive"))
    )
    (net (code "69") (name "Net-(LED28-PadA)") (class "Default")
      (node (ref "LED28") (pin "A") (pinfunction "A_A") (pintype "passive"))
      (node (ref "R28") (pin "1") (pinfunction "1_1") (pintype "passive"))
    )
    (net (code "70") (name "Net-(LED29-PadA)") (class "Default")
      (node (ref "LED29") (pin "A") (pinfunction "A_A") (pintype "passive"))
      (node (ref "R29") (pin "1") (pinfunction "1_1") (pintype "passive"))
    )
    (net (code "71") (name "Net-(LED30-PadA)") (class "Default")
      (node (ref "LED30") (pin "A") (pinfunction "A_A") (pintype "passive"))
      (node (ref "R30") (pin "1") (pinfunction "1_1") (pintype "passive"))
    )
    (net (code "72") (name "Net-(LED31-PadA)") (class "Default")
      (node (ref "LED31") (pin "A") (pinfunction "A_A") (pintype "passive"))
      (node (ref "R31") (pin "1") (pinfunction "1_1") (pintype "passive"))
    )
    (net (code "73") (name "Net-(LED32-PadA)") (class "Default")
      (node (ref "LED32") (pin "A") (pinfunction "A_A") (pintype "passive"))
      (node (ref "R32") (pin "1") (pinfunction "1_1") (pintype "passive"))
    )
    (net (code "74") (name "Net-(LED33-PadA)") (class "Default")
      (node (ref "LED33") (pin "A") (pinfunction "A_A") (pintype "passive"))
      (node (ref "R33") (pin "1") (pinfunction "1_1") (pintype "passive"))
    )
    (net (code "75") (name "Net-(LED34-PadA)") (class "Default")
      (node (ref "LED34") (pin "A") (pinfunction "A_A") (pintype "passive"))
      (node (ref "R34") (pin "1") (pinfunction "1_1") (pintype "passive"))
    )
    (net (code "76") (name "Net-(LED35-PadA)") (class "Default")
      (node (ref "LED35") (pin "A") (pinfunction "A_A") (pintype "passive"))
      (node (ref "R35") (pin "1") (pinfunction "1_1") (pintype "passive"))
    )
    (net (code "77") (name "Net-(LED36-PadA)") (class "Default")
      (node (ref "LED36") (pin "A") (pinfunction "A_A") (pintype "passive"))
      (node (ref "R36") (pin "1") (pinfunction "1_1") (pintype "passive"))
    )
    (net (code "78") (name "Net-(LED37-PadA)") (class "Default")
      (node (ref "LED37") (pin "A") (pinfunction "A_A") (pintype "passive"))
      (node (ref "R37") (pin "1") (pinfunction "1_1") (pintype "passive"))
    )
    (net (code "79") (name "Net-(LED38-PadA)") (class "Default")
      (node (ref "LED38") (pin "A") (pinfunction "A_A") (pintype "passive"))
      (node (ref "R38") (pin "1") (pinfunction "1_1") (pintype "passive"))
    )
    (net (code "80") (name "Net-(LED39-PadA)") (class "Default")
      (node (ref "LED39") (pin "A") (pinfunction "A_A") (pintype "passive"))
      (node (ref "R39") (pin "1") (pinfunction "1_1") (pintype "passive"))
    )
    (net (code "81") (name "Net-(LED40-PadA)") (class "Default")
      (node (ref "LED40") (pin "A") (pinfunction "A_A") (pintype "passive"))
      (node (ref "R40") (pin "1") (pinfunction "1_1") (pintype "passive"))
    )
    (net (code "82") (name "unconnected-(FTDI_2-Pad1)") (class "Default")
      (node (ref "FTDI_2") (pin "1") (pinfunction "1_1") (pintype "passive"))
    )
    (net (code "83") (name "unconnected-(FTDI_3-Pad1)") (class "Default")
      (node (ref "FTDI_3") (pin "1") (pinfunction "1_1") (pintype "passive"))
    )
    (net (code "84") (name "unconnected-(FTDI_6-Pad1)") (class "Default")
      (node (ref "FTDI_6") (pin "1") (pinfunction "1_1") (pintype "passive"))
    )
    (net (code "85") (name "unconnected-(FTDI_8-Pad1)") (class "Default")
      (node (ref "FTDI_8") (pin "1") (pinfunction "1_1") (pintype "passive"))
    )
    (net (code "86") (name "unconnected-(FTDI_9-Pad1)") (class "Default")
      (node (ref "FTDI_9") (pin "1") (pinfunction "1_1") (pintype "passive"))
    )
    (net (code "87") (name "unconnected-(FTDI_12-Pad1)") (class "Default")
      (node (ref "FTDI_12") (pin "1") (pinfunction "1_1") (pintype "passive"))
    )
  )
)
